# Power_supply.net
KiCad netlist of a schematic drawn in Altium Designer
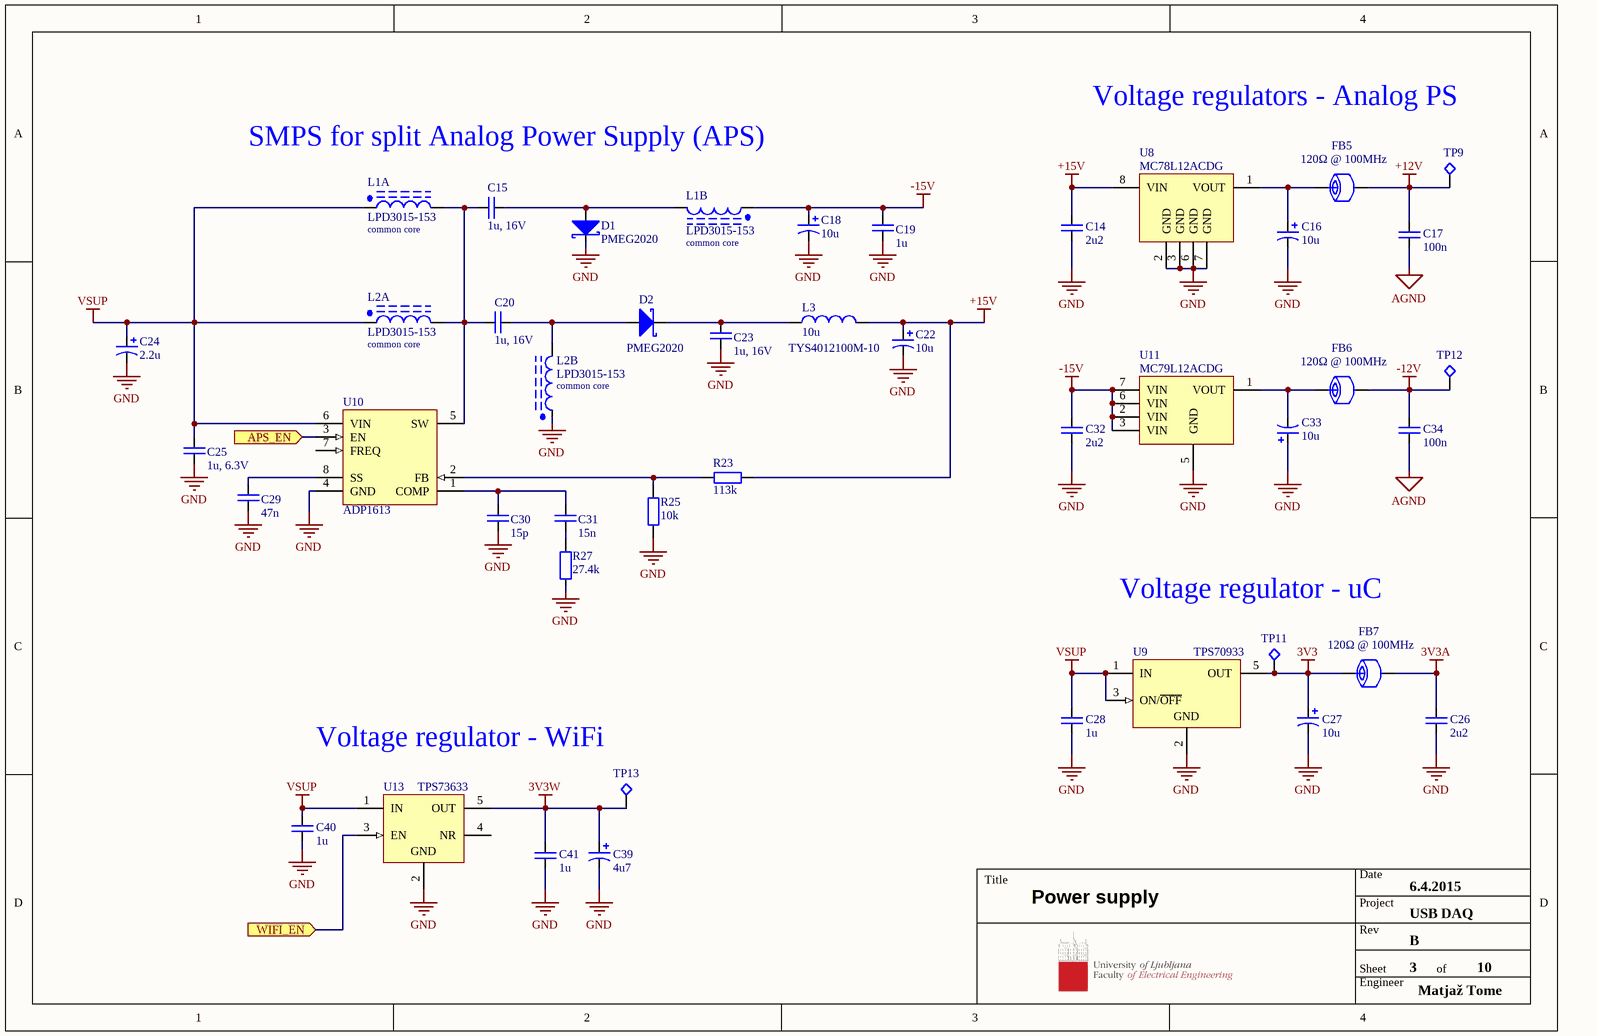
[diagram p0: Power_supply.SchDoc]

(export (version "E")
  (design (tool "Eeschema 10.0.6"))
  (components
    (comp (ref "C14")
      (value "2u2")
      (footprint "C_0603")
      (description "Generic capacitor")
      (fields (field (name "Comment") "comment"))
      (libsource (lib "DAQ") (part "Capacitor"))
    )
    (comp (ref "C15")
      (value "1u, 16V")
      (footprint "C_0603")
      (description "Generic capacitor")
      (fields (field (name "Comment") "comment"))
      (libsource (lib "DAQ") (part "Capacitor"))
    )
    (comp (ref "C16")
      (value "10u")
      (footprint "Tantalum Case A")
      (description "Generic polarized capacitor")
      (fields (field (name "Comment") "comment"))
      (libsource (lib "") (part "Capacitor - polarized_1"))
    )
    (comp (ref "C17")
      (value "100n")
      (footprint "C_0603")
      (description "Generic capacitor")
      (fields (field (name "Comment") "comment"))
      (libsource (lib "DAQ") (part "Capacitor"))
    )
    (comp (ref "C18")
      (value "10u")
      (footprint "Tantalum Case A")
      (description "Generic polarized capacitor")
      (fields (field (name "Comment") "comment"))
      (libsource (lib "DAQ") (part "Capacitor - polarized"))
    )
    (comp (ref "C19")
      (value "1u")
      (footprint "C_0603")
      (description "Generic capacitor")
      (fields (field (name "Comment") "comment"))
      (libsource (lib "DAQ") (part "Capacitor"))
    )
    (comp (ref "C20")
      (value "1u, 16V")
      (footprint "C_0603")
      (description "Generic capacitor")
      (fields (field (name "Comment") "comment"))
      (libsource (lib "DAQ") (part "Capacitor"))
    )
    (comp (ref "C22")
      (value "10u")
      (footprint "Tantalum Case A")
      (description "Generic polarized capacitor")
      (fields (field (name "Comment") "comment"))
      (libsource (lib "DAQ") (part "Capacitor - polarized"))
    )
    (comp (ref "C23")
      (value "1u, 16V")
      (footprint "C_0603")
      (description "Generic capacitor")
      (fields (field (name "Comment") "comment"))
      (libsource (lib "DAQ") (part "Capacitor"))
    )
    (comp (ref "C24")
      (value "2.2u")
      (footprint "Tantalum Case A")
      (description "Generic polarized capacitor")
      (fields (field (name "Comment") "comment"))
      (libsource (lib "DAQ") (part "Capacitor - polarized"))
    )
    (comp (ref "C25")
      (value "1u, 6.3V")
      (footprint "C_0603")
      (description "Generic capacitor")
      (fields (field (name "Comment") "comment"))
      (libsource (lib "DAQ") (part "Capacitor"))
    )
    (comp (ref "C26")
      (value "2u2")
      (footprint "C_0603")
      (description "Generic capacitor")
      (fields (field (name "Comment") "comment"))
      (libsource (lib "DAQ") (part "Capacitor"))
    )
    (comp (ref "C27")
      (value "10u")
      (footprint "Tantalum Case A")
      (description "Generic polarized capacitor")
      (fields (field (name "Comment") "comment"))
      (libsource (lib "") (part "Capacitor - polarized_1"))
    )
    (comp (ref "C28")
      (value "1u")
      (footprint "C_0603")
      (description "Generic capacitor")
      (fields (field (name "Comment") "comment"))
      (libsource (lib "DAQ") (part "Capacitor"))
    )
    (comp (ref "C29")
      (value "47n")
      (footprint "C_0603")
      (description "Generic capacitor")
      (fields (field (name "Comment") "comment"))
      (libsource (lib "DAQ") (part "Capacitor"))
    )
    (comp (ref "C30")
      (value "15p")
      (footprint "C_0603")
      (description "Generic capacitor")
      (fields (field (name "Comment") "comment"))
      (libsource (lib "DAQ") (part "Capacitor"))
    )
    (comp (ref "C31")
      (value "15n")
      (footprint "C_0603")
      (description "Generic capacitor")
      (fields (field (name "Comment") "comment"))
      (libsource (lib "DAQ") (part "Capacitor"))
    )
    (comp (ref "C32")
      (value "2u2")
      (footprint "C_0603")
      (description "Generic capacitor")
      (fields (field (name "Comment") "comment"))
      (libsource (lib "DAQ") (part "Capacitor"))
    )
    (comp (ref "C33")
      (value "10u")
      (footprint "Tantalum Case A")
      (description "Generic polarized capacitor")
      (fields (field (name "Comment") "comment"))
      (libsource (lib "") (part "Capacitor - polarized_1"))
    )
    (comp (ref "C34")
      (value "100n")
      (footprint "C_0603")
      (description "Generic capacitor")
      (fields (field (name "Comment") "comment"))
      (libsource (lib "DAQ") (part "Capacitor"))
    )
    (comp (ref "C39")
      (value "4u7")
      (footprint "Tantalum Case A")
      (description "Generic polarized capacitor")
      (fields (field (name "Comment") "comment"))
      (libsource (lib "") (part "Capacitor - polarized_1"))
    )
    (comp (ref "C40")
      (value "1u")
      (footprint "C_0603")
      (description "Generic capacitor")
      (fields (field (name "Comment") "comment"))
      (libsource (lib "DAQ") (part "Capacitor"))
    )
    (comp (ref "C41")
      (value "1u")
      (footprint "C_0603")
      (description "Generic capacitor")
      (fields (field (name "Comment") "comment"))
      (libsource (lib "DAQ") (part "Capacitor"))
    )
    (comp (ref "D1")
      (value "PMEG2020")
      (footprint "SOD323")
      (description "Schottky Rectifier, 20 V, 2 A, Single, SOD-323, 2 Pins, 525 mV")
      (fields (field (name "MANUFACTURER") "Infineon"))
      (libsource (lib "DAQ") (part "PMEG2020"))
    )
    (comp (ref "D2")
      (value "PMEG2020")
      (footprint "SOD323")
      (description "Schottky Rectifier, 20 V, 2 A, Single, SOD-323, 2 Pins, 525 mV")
      (fields (field (name "MANUFACTURER") "Infineon"))
      (libsource (lib "DAQ") (part "PMEG2020"))
    )
    (comp (ref "FB5")
      (value "120Ω @ 100MHz")
      (footprint "SMD_0805")
      (description "Ferrite Bead, 0805 [2012 Metric], 120 ohm, 800 mA, BLM21A Series, 0.15 ohm, ± 25%")
      (fields (field (name "MANUFACTURER") "Murata"))
      (libsource (lib "DAQ") (part "BLM21AG121SN1D"))
    )
    (comp (ref "FB6")
      (value "120Ω @ 100MHz")
      (footprint "SMD_0805")
      (description "Ferrite Bead, 0805 [2012 Metric], 120 ohm, 800 mA, BLM21A Series, 0.15 ohm, ± 25%")
      (fields (field (name "MANUFACTURER") "Murata"))
      (libsource (lib "DAQ") (part "BLM21AG121SN1D"))
    )
    (comp (ref "FB7")
      (value "120Ω @ 100MHz")
      (footprint "SMD_0805")
      (description "Ferrite Bead, 0805 [2012 Metric], 120 ohm, 800 mA, BLM21A Series, 0.15 ohm, ± 25%")
      (fields (field (name "MANUFACTURER") "Murata"))
      (libsource (lib "DAQ") (part "BLM21AG121SN1D"))
    )
    (comp (ref "L1")
      (value "LPD3015-153")
      (footprint "LPD3015")
      (description "Inductor, Coupled, 15 µH, 20%, 1.42 ohm, 460 mA, 3mm x 3mm x 1.4mm")
      (fields
        (field (name "MANUFACTURER") "Coilcraft")
        (field (name "TOLERANCE") "20%")
        (field (name "NOTE") "common core")
      )
      (libsource (lib "DAQ") (part "LPD3015-153"))
    )
    (comp (ref "L2")
      (value "LPD3015-153")
      (footprint "LPD3015")
      (description "Inductor, Coupled, 15 µH, 20%, 1.42 ohm, 460 mA, 3mm x 3mm x 1.4mm")
      (fields
        (field (name "MANUFACTURER") "Coilcraft")
        (field (name "TOLERANCE") "20%")
        (field (name "NOTE") "common core")
      )
      (libsource (lib "DAQ") (part "LPD3015-153"))
    )
    (comp (ref "L3")
      (value "10u")
      (footprint "IND_SMD_4X4mm")
      (description "Power Inductor (SMD), 10 µH, 770 mA, Shielded, 800 mA, TYS Series, 4mm x 4mm x 1.2mm")
      (fields
        (field (name "MANUFACTURER") "Laird Technologies")
        (field (name "TOLERANCE") "20%")
        (field (name "MANUFACTURER NUMBER") "TYS4012100M-10")
      )
      (libsource (lib "DAQ") (part "TYS4012100M-10"))
    )
    (comp (ref "R23")
      (value "113k")
      (footprint "R_0603")
      (description "Generic resistor")
      (fields (field (name "Comment") "comment"))
      (libsource (lib "DAQ") (part "Resistor"))
    )
    (comp (ref "R25")
      (value "10k")
      (footprint "R_0603")
      (description "Generic resistor")
      (fields (field (name "Comment") "comment"))
      (libsource (lib "DAQ") (part "Resistor"))
    )
    (comp (ref "R27")
      (value "27.4k")
      (footprint "R_0603")
      (description "Generic resistor")
      (fields (field (name "Comment") "comment"))
      (libsource (lib "DAQ") (part "Resistor"))
    )
    (comp (ref "TP9")
      (value "testpoint")
      (footprint "TP1_FULL")
      (description "testpoint 1.5mm diameter no hole")
      (fields (field (name "PART NUMBER") "XXC0006"))
      (libsource (lib "DAQ") (part "Test Point"))
    )
    (comp (ref "TP11")
      (value "testpoint")
      (footprint "TP1_FULL")
      (description "testpoint 1.5mm diameter no hole")
      (fields (field (name "PART NUMBER") "XXC0006"))
      (libsource (lib "DAQ") (part "Test Point"))
    )
    (comp (ref "TP12")
      (value "testpoint")
      (footprint "TP1_FULL")
      (description "testpoint 1.5mm diameter no hole")
      (fields (field (name "PART NUMBER") "XXC0006"))
      (libsource (lib "DAQ") (part "Test Point"))
    )
    (comp (ref "TP13")
      (value "testpoint")
      (footprint "TP1_FULL")
      (description "testpoint 1.5mm diameter no hole")
      (fields (field (name "PART NUMBER") "XXC0006"))
      (libsource (lib "DAQ") (part "Test Point"))
    )
    (comp (ref "U8")
      (value "MC78L12ACDG")
      (footprint "SOIC8")
      (description "100 mA Positive Voltage Regulator")
      (fields (field (name "PART NUMBER") "XLR0006") (field (name "MANUFACTURER") "ON Semiconductors"))
      (libsource (lib "DAQ") (part "78LXX"))
    )
    (comp (ref "U9")
      (value "TPS70933")
      (footprint "SOT23-5")
      (description "1-µA IQ Voltage Regulators with Enable")
      (fields (field (name "PART NUMBER") "XLR0012") (field (name "MANUFACTURER") "Texas Instruments"))
      (libsource (lib "DAQ") (part "TPS709XX"))
    )
    (comp (ref "U10")
      (value "ADP1613")
      (footprint "MSOP8")
      (description "DC-DC Switching Boost, SEPIC Regulator, Adjustable, 2.5V-5.5Vin, 3.6V-20Vout, 2Aout, MSOP-8")
      (fields (field (name "MANUFACTURER") "Analog devices"))
      (libsource (lib "DAQ") (part "ADP161X"))
    )
    (comp (ref "U11")
      (value "MC79L12ACDG")
      (footprint "SOIC8")
      (description "100 mA Negative Voltage Regulator")
      (fields (field (name "PART NUMBER") "XLR0007") (field (name "MANUFACTURER") "ON Semiconductors"))
      (libsource (lib "DAQ") (part "79LXX"))
    )
    (comp (ref "U13")
      (value "TPS73633")
      (footprint "SOT23-5")
      (description "Cap-Free, NMOS, 400-mA Low-Dropout Regulator with Reverse Current Protection")
      (fields (field (name "PART NUMBER") "XLR0013") (field (name "MANUFACTURER") "Texas instruments"))
      (libsource (lib "DAQ") (part "TPS736XX"))
    )
  )
  (nets
    (net (code "1") (name "+12V") (class "Default")
      (node (ref "C17") (pin "2") (pinfunction "2_2") (pintype "passive"))
      (node (ref "FB5") (pin "2") (pintype "passive"))
      (node (ref "TP9") (pin "1") (pinfunction "1_1") (pintype "passive"))
    )
    (net (code "2") (name "+15V") (class "Default")
      (node (ref "C14") (pin "1") (pinfunction "1_1") (pintype "passive"))
      (node (ref "C22") (pin "1") (pinfunction "1_1") (pintype "passive"))
      (node (ref "L3") (pin "2") (pinfunction "2_2") (pintype "passive"))
      (node (ref "R23") (pin "2") (pintype "passive"))
      (node (ref "U8") (pin "8") (pinfunction "VIN_8") (pintype "power_in"))
    )
    (net (code "3") (name "-12V") (class "Default")
      (node (ref "C34") (pin "2") (pinfunction "2_2") (pintype "passive"))
      (node (ref "FB6") (pin "2") (pintype "passive"))
      (node (ref "TP12") (pin "1") (pinfunction "1_1") (pintype "passive"))
    )
    (net (code "4") (name "-15V") (class "Default")
      (node (ref "C18") (pin "1") (pinfunction "1_1") (pintype "passive"))
      (node (ref "C19") (pin "1") (pinfunction "1_1") (pintype "passive"))
      (node (ref "C32") (pin "1") (pinfunction "1_1") (pintype "passive"))
      (node (ref "L1") (pin "4") (pinfunction "4_4") (pintype "passive"))
      (node (ref "U11") (pin "2") (pinfunction "VIN_2") (pintype "power_in"))
      (node (ref "U11") (pin "3") (pinfunction "VIN_3") (pintype "power_in"))
      (node (ref "U11") (pin "6") (pinfunction "VIN_6") (pintype "power_in"))
      (node (ref "U11") (pin "7") (pinfunction "VIN_7") (pintype "power_in"))
    )
    (net (code "5") (name "/APS_EN") (class "Default")
      (node (ref "U10") (pin "3") (pinfunction "EN_3") (pintype "input"))
    )
    (net (code "6") (name "/WIFI_EN") (class "Default")
      (node (ref "U13") (pin "3") (pinfunction "EN_3") (pintype "input"))
    )
    (net (code "7") (name "3V3") (class "Default")
      (node (ref "C27") (pin "1") (pinfunction "1_1") (pintype "passive"))
      (node (ref "FB7") (pin "1") (pintype "passive"))
      (node (ref "TP11") (pin "1") (pinfunction "1_1") (pintype "passive"))
      (node (ref "U9") (pin "5") (pinfunction "OUT_5") (pintype "power_in"))
    )
    (net (code "8") (name "3V3A") (class "Default")
      (node (ref "C26") (pin "1") (pinfunction "1_1") (pintype "passive"))
      (node (ref "FB7") (pin "2") (pintype "passive"))
    )
    (net (code "9") (name "3V3W") (class "Default")
      (node (ref "C39") (pin "1") (pinfunction "1_1") (pintype "passive"))
      (node (ref "C41") (pin "1") (pinfunction "1_1") (pintype "passive"))
      (node (ref "TP13") (pin "1") (pinfunction "1_1") (pintype "passive"))
      (node (ref "U13") (pin "5") (pinfunction "OUT_5") (pintype "power_in"))
    )
    (net (code "10") (name "AGND") (class "Default")
      (node (ref "C17") (pin "1") (pinfunction "1_1") (pintype "passive"))
      (node (ref "C34") (pin "1") (pinfunction "1_1") (pintype "passive"))
    )
    (net (code "11") (name "GND") (class "Default")
      (node (ref "C14") (pin "2") (pinfunction "2_2") (pintype "passive"))
      (node (ref "C16") (pin "2") (pinfunction "2_2") (pintype "passive"))
      (node (ref "C18") (pin "2") (pinfunction "2_2") (pintype "passive"))
      (node (ref "C19") (pin "2") (pinfunction "2_2") (pintype "passive"))
      (node (ref "C22") (pin "2") (pinfunction "2_2") (pintype "passive"))
      (node (ref "C23") (pin "2") (pinfunction "2_2") (pintype "passive"))
      (node (ref "C24") (pin "2") (pinfunction "2_2") (pintype "passive"))
      (node (ref "C25") (pin "1") (pinfunction "1_1") (pintype "passive"))
      (node (ref "C26") (pin "2") (pinfunction "2_2") (pintype "passive"))
      (node (ref "C27") (pin "2") (pinfunction "2_2") (pintype "passive"))
      (node (ref "C28") (pin "2") (pinfunction "2_2") (pintype "passive"))
      (node (ref "C29") (pin "2") (pinfunction "2_2") (pintype "passive"))
      (node (ref "C30") (pin "1") (pinfunction "1_1") (pintype "passive"))
      (node (ref "C32") (pin "2") (pinfunction "2_2") (pintype "passive"))
      (node (ref "C33") (pin "1") (pinfunction "1_1") (pintype "passive"))
      (node (ref "C39") (pin "2") (pinfunction "2_2") (pintype "passive"))
      (node (ref "C40") (pin "2") (pinfunction "2_2") (pintype "passive"))
      (node (ref "C41") (pin "2") (pinfunction "2_2") (pintype "passive"))
      (node (ref "D1") (pin "2") (pinfunction "K_2") (pintype "passive"))
      (node (ref "L2") (pin "4") (pinfunction "4_4") (pintype "passive"))
      (node (ref "R25") (pin "2") (pintype "passive"))
      (node (ref "R27") (pin "1") (pintype "passive"))
      (node (ref "U10") (pin "4") (pinfunction "GND_4") (pintype "power_in"))
      (node (ref "U11") (pin "5") (pinfunction "GND_5") (pintype "power_in"))
      (node (ref "U13") (pin "2") (pinfunction "GND_2") (pintype "power_in"))
      (node (ref "U8") (pin "2") (pinfunction "GND_2") (pintype "power_in"))
      (node (ref "U8") (pin "3") (pinfunction "GND_3") (pintype "power_in"))
      (node (ref "U8") (pin "6") (pinfunction "GND_6") (pintype "power_in"))
      (node (ref "U8") (pin "7") (pinfunction "GND_7") (pintype "power_in"))
      (node (ref "U9") (pin "2") (pinfunction "GND_2") (pintype "power_in"))
    )
    (net (code "12") (name "Net-(C31-Pad1)") (class "Default")
      (node (ref "C31") (pin "1") (pinfunction "1_1") (pintype "passive"))
      (node (ref "R27") (pin "2") (pintype "passive"))
    )
    (net (code "13") (name "Net-(D1-A)") (class "Default")
      (node (ref "C15") (pin "1") (pinfunction "1_1") (pintype "passive"))
      (node (ref "D1") (pin "1") (pinfunction "A_1") (pintype "passive"))
      (node (ref "L1") (pin "3") (pinfunction "3_3") (pintype "passive"))
    )
    (net (code "14") (name "Net-(D2-A)") (class "Default")
      (node (ref "C20") (pin "2") (pinfunction "2_2") (pintype "passive"))
      (node (ref "D2") (pin "1") (pinfunction "A_1") (pintype "passive"))
      (node (ref "L2") (pin "3") (pinfunction "3_3") (pintype "passive"))
    )
    (net (code "15") (name "Net-(D2-K)") (class "Default")
      (node (ref "C23") (pin "1") (pinfunction "1_1") (pintype "passive"))
      (node (ref "D2") (pin "2") (pinfunction "K_2") (pintype "passive"))
      (node (ref "L3") (pin "1") (pinfunction "1_1") (pintype "passive"))
    )
    (net (code "16") (name "Net-(U8-VOUT)") (class "Default")
      (node (ref "C16") (pin "1") (pinfunction "1_1") (pintype "passive"))
      (node (ref "FB5") (pin "1") (pintype "passive"))
      (node (ref "U8") (pin "1") (pinfunction "VOUT_1") (pintype "power_in"))
    )
    (net (code "17") (name "Net-(U10-COMP)") (class "Default")
      (node (ref "C30") (pin "2") (pinfunction "2_2") (pintype "passive"))
      (node (ref "C31") (pin "2") (pinfunction "2_2") (pintype "passive"))
      (node (ref "U10") (pin "1") (pinfunction "COMP_1") (pintype "passive"))
    )
    (net (code "18") (name "Net-(U10-FB)") (class "Default")
      (node (ref "R23") (pin "1") (pintype "passive"))
      (node (ref "R25") (pin "1") (pintype "passive"))
      (node (ref "U10") (pin "2") (pinfunction "FB_2") (pintype "input"))
    )
    (net (code "19") (name "Net-(U10-SS)") (class "Default")
      (node (ref "C29") (pin "1") (pinfunction "1_1") (pintype "passive"))
      (node (ref "U10") (pin "8") (pinfunction "SS_8") (pintype "passive"))
    )
    (net (code "20") (name "Net-(U10-SW)") (class "Default")
      (node (ref "C15") (pin "2") (pinfunction "2_2") (pintype "passive"))
      (node (ref "C20") (pin "1") (pinfunction "1_1") (pintype "passive"))
      (node (ref "L1") (pin "2") (pinfunction "2_2") (pintype "passive"))
      (node (ref "L2") (pin "2") (pinfunction "2_2") (pintype "passive"))
      (node (ref "U10") (pin "5") (pinfunction "SW_5") (pintype "passive"))
    )
    (net (code "21") (name "Net-(U11-VOUT)") (class "Default")
      (node (ref "C33") (pin "2") (pinfunction "2_2") (pintype "passive"))
      (node (ref "FB6") (pin "1") (pintype "passive"))
      (node (ref "U11") (pin "1") (pinfunction "VOUT_1") (pintype "power_in"))
    )
    (net (code "22") (name "VSUP") (class "Default")
      (node (ref "C24") (pin "1") (pinfunction "1_1") (pintype "passive"))
      (node (ref "C25") (pin "2") (pinfunction "2_2") (pintype "passive"))
      (node (ref "C28") (pin "1") (pinfunction "1_1") (pintype "passive"))
      (node (ref "C40") (pin "1") (pinfunction "1_1") (pintype "passive"))
      (node (ref "L1") (pin "1") (pinfunction "1_1") (pintype "passive"))
      (node (ref "L2") (pin "1") (pinfunction "1_1") (pintype "passive"))
      (node (ref "U10") (pin "6") (pinfunction "VIN_6") (pintype "power_in"))
      (node (ref "U13") (pin "1") (pinfunction "IN_1") (pintype "power_in"))
      (node (ref "U9") (pin "1") (pinfunction "IN_1") (pintype "power_in"))
      (node (ref "U9") (pin "3") (pinfunction "ON/~{OFF}_3") (pintype "input"))
    )
    (net (code "23") (name "unconnected-(U10-FREQ-Pad7)") (class "Default")
      (node (ref "U10") (pin "7") (pinfunction "FREQ_7") (pintype "input"))
    )
    (net (code "24") (name "unconnected-(U13-NR-Pad4)") (class "Default")
      (node (ref "U13") (pin "4") (pinfunction "NR_4") (pintype "passive"))
    )
  )
)
